# Power_DCDC.net
KiCad netlist of a schematic drawn in Altium Designer
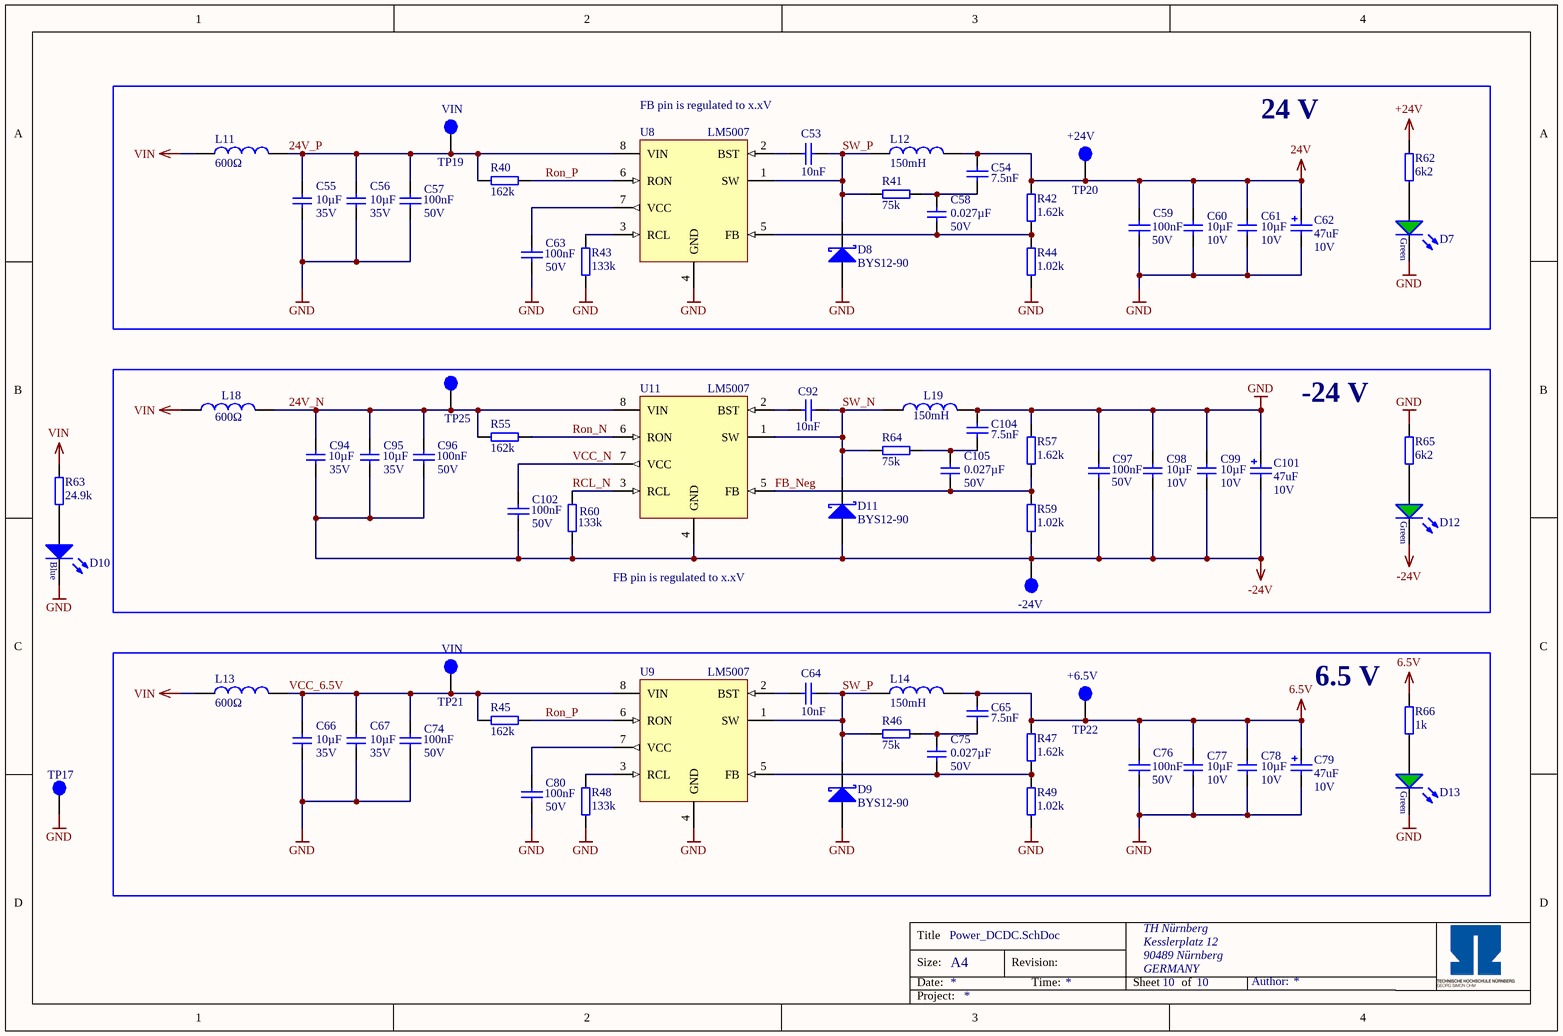
[diagram p0: Power_DCDC.SchDoc]

(export (version "E")
  (design (tool "Eeschema 10.0.6"))
  (components
    (comp (ref "-24V")
      (value "-6.5V")
      (footprint "TP_1mm")
      (description "Testpoint 1mm")
      (fields (field (name "CREATED") "2018_06_25_AGeiger"))
      (libsource (lib "UltraZohm_ADC") (part "TP_1mm"))
    )
    (comp (ref "C53")
      (value "10nF")
      (footprint "CAPC1608X07N")
      (fields (field (name "MF") "Würth") (field (name "MPN") "885012206065") (field (name "VOLTAGE") "25V"))
      (libsource (lib "UltraZohm_ADC") (part "Cap_0603"))
    )
    (comp (ref "C54")
      (value "7.5nF")
      (footprint "CAPC1608X07N")
      (fields
        (field (name "MF") "KEMET")
        (field (name "MPN") "C0603C752J3GACTU")
        (field (name "VOLTAGE") "25V")
      )
      (libsource (lib "UltraZohm_ADC") (part "Cap_0603"))
    )
    (comp (ref "C55")
      (value "10µF")
      (footprint "C_1206")
      (description "Capacitor 1206")
      (fields (field (name "TOLERANCE") "20%") (field (name "MF") "AVX") (field (name "VOLTAGE") "35V"))
      (libsource (lib "UltraZohm_ADC") (part "C_1206"))
    )
    (comp (ref "C56")
      (value "10µF")
      (footprint "C_1206")
      (description "Capacitor 1206")
      (fields (field (name "TOLERANCE") "20%") (field (name "MF") "AVX") (field (name "VOLTAGE") "35V"))
      (libsource (lib "UltraZohm_ADC") (part "C_1206"))
    )
    (comp (ref "C57")
      (value "100nF")
      (footprint "CAPC1608X07N")
      (fields
        (field (name "MF") "Yageo")
        (field (name "MPN") "CC0603KRX7R9BB104")
        (field (name "VOLTAGE") "50V")
        (field (name "TOLERANCE") "10%")
      )
      (libsource (lib "UltraZohm_ADC") (part "Cap_0603"))
    )
    (comp (ref "C58")
      (value "0.027µF")
      (footprint "C_1206")
      (description "Capacitor 1206")
      (fields
        (field (name "TOLERANCE") "5%")
        (field (name "MF") "Murata")
        (field (name "VOLTAGE") "50V")
        (field (name "CREATED") "2018_06_25_AGeiger")
      )
      (libsource (lib "UltraZohm_ADC") (part "C_1206"))
    )
    (comp (ref "C59")
      (value "100nF")
      (footprint "CAPC1608X07N")
      (fields
        (field (name "MF") "Yageo")
        (field (name "MPN") "CC0603KRX7R9BB104")
        (field (name "VOLTAGE") "50V")
      )
      (libsource (lib "UltraZohm_ADC") (part "Cap_0603"))
    )
    (comp (ref "C60")
      (value "10µF")
      (footprint "C_1206")
      (description "Capacitor 1206")
      (fields
        (field (name "TOLERANCE") "10%")
        (field (name "MF") "Samsung Electro-Mechanics")
        (field (name "VOLTAGE") "10V")
        (field (name "CREATED") "2020_09_17_Liegmann")
      )
      (libsource (lib "UltraZohm_ADC") (part "C_1206"))
    )
    (comp (ref "C61")
      (value "10µF")
      (footprint "C_1206")
      (description "Capacitor 1206")
      (fields
        (field (name "TOLERANCE") "10%")
        (field (name "MF") "Samsung Electro-Mechanics")
        (field (name "VOLTAGE") "10V")
        (field (name "CREATED") "2020_09_17_Liegmann")
      )
      (libsource (lib "UltraZohm_ADC") (part "C_1206"))
    )
    (comp (ref "C62")
      (value "47uF")
      (footprint "WCAP-ASLI_5x5.5")
      (description "WCAP-ASLI Aluminum Electrolytic Capacitor, V-Chip, SMT, D5xH5.5mm, 47uF, 10V")
      (fields
        (field (name "MPN") "865080242004")
        (field (name "MF") "Wurth Elektronik")
        (field (name "VOLTAGE") "10V")
      )
      (libsource (lib "UltraZohm_ADC") (part "865080142007"))
    )
    (comp (ref "C63")
      (value "100nF")
      (footprint "CAPC1608X07N")
      (fields
        (field (name "MF") "Yageo")
        (field (name "MPN") "CC0603KRX7R9BB104")
        (field (name "VOLTAGE") "50V")
        (field (name "TOLERANCE") "10%")
      )
      (libsource (lib "UltraZohm_ADC") (part "Cap_0603"))
    )
    (comp (ref "C64")
      (value "10nF")
      (footprint "CAPC1608X07N")
      (fields (field (name "MF") "Würth") (field (name "MPN") "885012206065") (field (name "VOLTAGE") "25V"))
      (libsource (lib "UltraZohm_ADC") (part "Cap_0603"))
    )
    (comp (ref "C65")
      (value "7.5nF")
      (footprint "CAPC1608X07N")
      (fields
        (field (name "MF") "KEMET")
        (field (name "MPN") "C0603C752J3GACTU")
        (field (name "VOLTAGE") "25V")
      )
      (libsource (lib "UltraZohm_ADC") (part "Cap_0603"))
    )
    (comp (ref "C66")
      (value "10µF")
      (footprint "C_1206")
      (description "Capacitor 1206")
      (fields (field (name "TOLERANCE") "20%") (field (name "MF") "AVX") (field (name "VOLTAGE") "35V"))
      (libsource (lib "UltraZohm_ADC") (part "C_1206"))
    )
    (comp (ref "C67")
      (value "10µF")
      (footprint "C_1206")
      (description "Capacitor 1206")
      (fields (field (name "TOLERANCE") "20%") (field (name "MF") "AVX") (field (name "VOLTAGE") "35V"))
      (libsource (lib "UltraZohm_ADC") (part "C_1206"))
    )
    (comp (ref "C74")
      (value "100nF")
      (footprint "CAPC1608X07N")
      (fields
        (field (name "MF") "Yageo")
        (field (name "MPN") "CC0603KRX7R9BB104")
        (field (name "VOLTAGE") "50V")
        (field (name "TOLERANCE") "10%")
      )
      (libsource (lib "UltraZohm_ADC") (part "Cap_0603"))
    )
    (comp (ref "C75")
      (value "0.027µF")
      (footprint "C_1206")
      (description "Capacitor 1206")
      (fields
        (field (name "TOLERANCE") "5%")
        (field (name "MF") "Murata")
        (field (name "VOLTAGE") "50V")
        (field (name "CREATED") "2018_06_25_AGeiger")
      )
      (libsource (lib "UltraZohm_ADC") (part "C_1206"))
    )
    (comp (ref "C76")
      (value "100nF")
      (footprint "CAPC1608X07N")
      (fields
        (field (name "MF") "Yageo")
        (field (name "MPN") "CC0603KRX7R9BB104")
        (field (name "VOLTAGE") "50V")
      )
      (libsource (lib "UltraZohm_ADC") (part "Cap_0603"))
    )
    (comp (ref "C77")
      (value "10µF")
      (footprint "C_1206")
      (description "Capacitor 1206")
      (fields
        (field (name "TOLERANCE") "10%")
        (field (name "MF") "Samsung Electro-Mechanics")
        (field (name "VOLTAGE") "10V")
        (field (name "CREATED") "2020_09_17_Liegmann")
      )
      (libsource (lib "UltraZohm_ADC") (part "C_1206"))
    )
    (comp (ref "C78")
      (value "10µF")
      (footprint "C_1206")
      (description "Capacitor 1206")
      (fields
        (field (name "TOLERANCE") "10%")
        (field (name "MF") "Samsung Electro-Mechanics")
        (field (name "VOLTAGE") "10V")
        (field (name "CREATED") "2020_09_17_Liegmann")
      )
      (libsource (lib "UltraZohm_ADC") (part "C_1206"))
    )
    (comp (ref "C79")
      (value "47uF")
      (footprint "WCAP-ASLI_5x5.5")
      (description "WCAP-ASLI Aluminum Electrolytic Capacitor, V-Chip, SMT, D5xH5.5mm, 47uF, 10V")
      (fields
        (field (name "MPN") "865080242004")
        (field (name "MF") "Wurth Elektronik")
        (field (name "VOLTAGE") "10V")
      )
      (libsource (lib "UltraZohm_ADC") (part "865080142007"))
    )
    (comp (ref "C80")
      (value "100nF")
      (footprint "CAPC1608X07N")
      (fields
        (field (name "MF") "Yageo")
        (field (name "MPN") "CC0603KRX7R9BB104")
        (field (name "VOLTAGE") "50V")
        (field (name "TOLERANCE") "10%")
      )
      (libsource (lib "UltraZohm_ADC") (part "Cap_0603"))
    )
    (comp (ref "C92")
      (value "10nF")
      (footprint "CAPC1608X07N")
      (fields
        (field (name "MF") "Würth Elektronik")
        (field (name "MPN") "885012206065")
        (field (name "VOLTAGE") "25V")
      )
      (libsource (lib "UltraZohm_ADC") (part "Cap_0603"))
    )
    (comp (ref "C94")
      (value "10µF")
      (footprint "C_1206")
      (description "Capacitor 1206")
      (fields (field (name "TOLERANCE") "20%") (field (name "MF") "AVX") (field (name "VOLTAGE") "35V"))
      (libsource (lib "UltraZohm_ADC") (part "C_1206"))
    )
    (comp (ref "C95")
      (value "10µF")
      (footprint "C_1206")
      (description "Capacitor 1206")
      (fields (field (name "TOLERANCE") "20%") (field (name "MF") "AVX") (field (name "VOLTAGE") "35V"))
      (libsource (lib "UltraZohm_ADC") (part "C_1206"))
    )
    (comp (ref "C96")
      (value "100nF")
      (footprint "CAPC1608X07N")
      (fields
        (field (name "MF") "Yageo")
        (field (name "MPN") "CC0603KRX7R9BB104")
        (field (name "VOLTAGE") "50V")
        (field (name "TOLERANCE") "10%")
      )
      (libsource (lib "UltraZohm_ADC") (part "Cap_0603"))
    )
    (comp (ref "C97")
      (value "100nF")
      (footprint "CAPC1608X07N")
      (fields
        (field (name "MF") "Yageo")
        (field (name "MPN") "CC0603KRX7R9BB104")
        (field (name "VOLTAGE") "50V")
        (field (name "TOLERANCE") "10%")
      )
      (libsource (lib "UltraZohm_ADC") (part "Cap_0603"))
    )
    (comp (ref "C98")
      (value "10µF")
      (footprint "C_1206")
      (description "Capacitor 1206")
      (fields
        (field (name "TOLERANCE") "10%")
        (field (name "MF") "Samsung Electro-Mechanics")
        (field (name "VOLTAGE") "10V")
        (field (name "CREATED") "2020_09_17_Liegmann")
      )
      (libsource (lib "UltraZohm_ADC") (part "C_1206"))
    )
    (comp (ref "C99")
      (value "10µF")
      (footprint "C_1206")
      (description "Capacitor 1206")
      (fields
        (field (name "TOLERANCE") "10%")
        (field (name "MF") "Samsung Electro-Mechanics")
        (field (name "VOLTAGE") "10V")
        (field (name "CREATED") "2020_09_17_Liegmann")
      )
      (libsource (lib "UltraZohm_ADC") (part "C_1206"))
    )
    (comp (ref "C101")
      (value "47uF")
      (footprint "WCAP-ASLI_5x5.5")
      (description "WCAP-ASLI Aluminum Electrolytic Capacitor, V-Chip, SMT, D5xH5.5mm, 47uF, 10V")
      (fields
        (field (name "MPN") "865080242004")
        (field (name "MF") "Wurth Elektronik")
        (field (name "VOLTAGE") "10V")
      )
      (libsource (lib "UltraZohm_ADC") (part "865080142007"))
    )
    (comp (ref "C102")
      (value "100nF")
      (footprint "CAPC1608X07N")
      (fields
        (field (name "MF") "Yageo")
        (field (name "MPN") "CC0603KRX7R9BB104")
        (field (name "VOLTAGE") "50V")
        (field (name "TOLERANCE") "10%")
      )
      (libsource (lib "UltraZohm_ADC") (part "Cap_0603"))
    )
    (comp (ref "C104")
      (value "7.5nF")
      (footprint "CAPC1608X07N")
      (fields
        (field (name "MF") "KEMET")
        (field (name "MPN") "C0603C752J3GACTU")
        (field (name "VOLTAGE") "25V")
      )
      (libsource (lib "UltraZohm_ADC") (part "Cap_0603"))
    )
    (comp (ref "C105")
      (value "0.027µF")
      (footprint "C_1206")
      (description "Capacitor 1206")
      (fields
        (field (name "TOLERANCE") "5%")
        (field (name "MF") "Murata")
        (field (name "VOLTAGE") "50V")
        (field (name "CREATED") "2018_06_25_AGeiger")
      )
      (libsource (lib "UltraZohm_ADC") (part "C_1206"))
    )
    (comp (ref "D7")
      (value "150060GS75000")
      (footprint "WL-SMCW_0603")
      (description "WL-SMCW SMD Mono-color Chip LED Waterclear, size 0603, Green, 3.2 V, 140°")
      (fields (field (name "MF") "Wuerth Elektronik") (field (name "CREATED") "2018_09_06_AGeiger"))
      (libsource (lib "UltraZohm_ADC") (part "LED_Green_0603"))
    )
    (comp (ref "D8")
      (value "BYS12-90")
      (footprint "DIOM4227X23N")
      (description "Schottky Diode")
      (fields (field (name "MF") "Vishay") (field (name "MPN") "BYS12-90-E3/TR3"))
      (libsource (lib "UltraZohm_ADC") (part "BYS12-90"))
    )
    (comp (ref "D9")
      (value "BYS12-90")
      (footprint "DIOM4227X23N")
      (description "Schottky Diode")
      (fields (field (name "MF") "Vishay") (field (name "MPN") "BYS12-90-E3/TR3"))
      (libsource (lib "UltraZohm_ADC") (part "BYS12-90"))
    )
    (comp (ref "D10")
      (value "150060BS75000")
      (footprint "WL-SMCW_0603")
      (description "WL-SMCW SMD Mono-color Chip LED Waterclear, size 0603, Blue, 3.2 V, 140°")
      (fields (field (name "MF") "Wuerth Elektronik") (field (name "CREATED") "2018_09_06_AGeiger"))
      (libsource (lib "UltraZohm_ADC") (part "LED_Blue_0603"))
    )
    (comp (ref "D11")
      (value "BYS12-90")
      (footprint "DIOM4227X23N")
      (description "Schottky Diode")
      (fields (field (name "MF") "Vishay") (field (name "MPN") "BYS12-90-E3/TR3"))
      (libsource (lib "UltraZohm_ADC") (part "BYS12-90"))
    )
    (comp (ref "D12")
      (value "150060GS75000")
      (footprint "WL-SMCW_0603")
      (description "WL-SMCW SMD Mono-color Chip LED Waterclear, size 0603, Green, 3.2 V, 140°")
      (fields (field (name "MF") "Wuerth Elektronik") (field (name "CREATED") "2018_09_06_AGeiger"))
      (libsource (lib "UltraZohm_ADC") (part "LED_Green_0603"))
    )
    (comp (ref "D13")
      (value "150060GS75000")
      (footprint "WL-SMCW_0603")
      (description "WL-SMCW SMD Mono-color Chip LED Waterclear, size 0603, Green, 3.2 V, 140°")
      (fields (field (name "MF") "Wuerth Elektronik") (field (name "CREATED") "2018_09_06_AGeiger"))
      (libsource (lib "UltraZohm_ADC") (part "LED_Green_0603"))
    )
    (comp (ref "L11")
      (value "600Ω")
      (footprint "WE-CBF_0805_High Current")
      (description "WE-CBF SMD EMI Suppression Ferrite Bead, 0805, 600Ω")
      (fields (field (name "MF") "Wurth Elektronik") (field (name "MPN") "742792040"))
      (libsource (lib "UltraZohm_ADC") (part "WE-CBF, 742792040"))
    )
    (comp (ref "L12")
      (value "150mH")
      (footprint "SMT_inductor_1050_Performance")
      (description "SMT power Inductor, 150uH, 320m DRC")
      (fields (field (name "MF") "EPCOS / TDK") (field (name "MPN") "B82464G4154M"))
      (libsource (lib "UltraZohm_ADC") (part "B82464G4154M"))
    )
    (comp (ref "L13")
      (value "600Ω")
      (footprint "WE-CBF_0805_High Current")
      (description "WE-CBF SMD EMI Suppression Ferrite Bead, 0805, 600Ω")
      (fields (field (name "MF") "Wurth Elektronik") (field (name "MPN") "742792040"))
      (libsource (lib "UltraZohm_ADC") (part "WE-CBF, 742792040"))
    )
    (comp (ref "L14")
      (value "150mH")
      (footprint "SMT_inductor_1050_Performance")
      (description "SMT power Inductor, 150uH, 320m DRC")
      (fields (field (name "MF") "EPCOS / TDK") (field (name "MPN") "B82464G4154M"))
      (libsource (lib "UltraZohm_ADC") (part "B82464G4154M"))
    )
    (comp (ref "L18")
      (value "600Ω")
      (footprint "WE-CBF_0805_High Current")
      (description "WE-CBF SMD EMI Suppression Ferrite Bead, 0805, 600Ω")
      (fields (field (name "MF") "Würth Elektronik") (field (name "MPN") "742792040"))
      (libsource (lib "UltraZohm_ADC") (part "WE-CBF, 742792040"))
    )
    (comp (ref "L19")
      (value "150mH")
      (footprint "SMT_inductor_1050_Performance")
      (description "SMT power Inductor, 150uH, 320m DRC")
      (fields (field (name "MF") "EPCOS / TDK") (field (name "MPN") "B82464G4154M"))
      (libsource (lib "UltraZohm_ADC") (part "B82464G4154M"))
    )
    (comp (ref "R40")
      (value "162k")
      (footprint "RESC1608X06N")
      (fields (field (name "MF") "Bourns") (field (name "MPN") "CR0603-FX-1623ELF"))
      (libsource (lib "UltraZohm_ADC") (part "R_0603"))
    )
    (comp (ref "R41")
      (value "75k")
      (footprint "RESC1608X06N")
      (fields (field (name "MF") "Yageo") (field (name "MPN") "AC0603FR-1375KL"))
      (libsource (lib "UltraZohm_ADC") (part "R_0603"))
    )
    (comp (ref "R42")
      (value "1.62k")
      (footprint "RESC1608X06N")
      (fields
        (field (name "MF") "Bourns")
        (field (name "MPN") "CR0603-FX-1621ELF")
        (field (name "TOLERANCE") "1%")
      )
      (libsource (lib "UltraZohm_ADC") (part "R_0603"))
    )
    (comp (ref "R43")
      (value "133k")
      (footprint "RESC1608X06N")
      (fields (field (name "MF") "Bourns") (field (name "MPN") "CR0603-FX-1333ELF"))
      (libsource (lib "UltraZohm_ADC") (part "R_0603"))
    )
    (comp (ref "R44")
      (value "1.02k")
      (footprint "RESC1608X06N")
      (fields
        (field (name "MF") "Bourns")
        (field (name "MPN") "CR0603-FX-1021ELF")
        (field (name "TOLERANCE") "1%")
      )
      (libsource (lib "UltraZohm_ADC") (part "R_0603"))
    )
    (comp (ref "R45")
      (value "162k")
      (footprint "RESC1608X06N")
      (fields (field (name "MF") "Bourns") (field (name "MPN") "CR0603-FX-1623ELF"))
      (libsource (lib "UltraZohm_ADC") (part "R_0603"))
    )
    (comp (ref "R46")
      (value "75k")
      (footprint "RESC1608X06N")
      (fields (field (name "MF") "Yageo") (field (name "MPN") "AC0603FR-1375KL"))
      (libsource (lib "UltraZohm_ADC") (part "R_0603"))
    )
    (comp (ref "R47")
      (value "1.62k")
      (footprint "RESC1608X06N")
      (fields
        (field (name "MF") "Bourns")
        (field (name "MPN") "CR0603-FX-1621ELF")
        (field (name "TOLERANCE") "1%")
      )
      (libsource (lib "UltraZohm_ADC") (part "R_0603"))
    )
    (comp (ref "R48")
      (value "133k")
      (footprint "RESC1608X06N")
      (fields (field (name "MF") "Bourns") (field (name "MPN") "CR0603-FX-1333ELF"))
      (libsource (lib "UltraZohm_ADC") (part "R_0603"))
    )
    (comp (ref "R49")
      (value "1.02k")
      (footprint "RESC1608X06N")
      (fields
        (field (name "MF") "Bourns")
        (field (name "MPN") "CR0603-FX-1021ELF")
        (field (name "TOLERANCE") "1%")
      )
      (libsource (lib "UltraZohm_ADC") (part "R_0603"))
    )
    (comp (ref "R55")
      (value "162k")
      (footprint "RESC1608X06N")
      (fields (field (name "MF") "Bourns") (field (name "MPN") "CR0603-FX-1623ELF"))
      (libsource (lib "UltraZohm_ADC") (part "R_0603"))
    )
    (comp (ref "R57")
      (value "1.62k")
      (footprint "RESC1608X06N")
      (fields
        (field (name "MF") "Bourns")
        (field (name "MPN") "CR0603-FX-1621ELF")
        (field (name "TOLERANCE") "1%")
      )
      (libsource (lib "UltraZohm_ADC") (part "R_0603"))
    )
    (comp (ref "R59")
      (value "1.02k")
      (footprint "RESC1608X06N")
      (fields
        (field (name "MF") "Bourns")
        (field (name "MPN") "CR0603-FX-1021ELF")
        (field (name "TOLERANCE") "1%")
      )
      (libsource (lib "UltraZohm_ADC") (part "R_0603"))
    )
    (comp (ref "R60")
      (value "133k")
      (footprint "RESC1608X06N")
      (fields (field (name "MF") "Bourns") (field (name "MPN") "CR0603-FX-1333ELF"))
      (libsource (lib "UltraZohm_ADC") (part "R_0603"))
    )
    (comp (ref "R62")
      (value "6k2")
      (footprint "RES 0603_1608")
      (description "SMD resistor E24 series")
      (fields
        (field (name "MANUFACTURER PART NUMBER") "RK73B1JTTD622J")
        (field (name "MANUFACTURER") "KOA Speer")
        (field (name "CREATED FROM") "MGremer")
      )
      (libsource (lib "user") (part "Resistor"))
    )
    (comp (ref "R63")
      (value "24.9k")
      (footprint "RESC1608X06N")
      (fields (field (name "MF") "Vishay / Dale") (field (name "MPN") "CRCW060324K9FKEAC"))
      (libsource (lib "UltraZohm_ADC") (part "R_0603"))
    )
    (comp (ref "R64")
      (value "75k")
      (footprint "RESC1608X06N")
      (fields (field (name "MF") "Yageo") (field (name "MPN") "AC0603FR-1375KL"))
      (libsource (lib "UltraZohm_ADC") (part "R_0603"))
    )
    (comp (ref "R65")
      (value "6k2")
      (footprint "RES 0603_1608")
      (description "SMD resistor E24 series")
      (fields
        (field (name "MANUFACTURER PART NUMBER") "RK73B1JTTD622J")
        (field (name "MANUFACTURER") "KOA Speer")
        (field (name "CREATED FROM") "MGremer")
      )
      (libsource (lib "user") (part "Resistor"))
    )
    (comp (ref "R66")
      (value "1k")
      (footprint "RES 0603_1608")
      (description "SMD resistor E24 series")
      (fields
        (field (name "MANUFACTURER PART NUMBER") "RK73B1JTTDD102J")
        (field (name "MANUFACTURER") "KOA Speer")
        (field (name "CREATED FROM") "MGremer")
      )
      (libsource (lib "user") (part "Resistor"))
    )
    (comp (ref "TP17")
      (value "GND")
      (footprint "TP_1mm")
      (description "Testpoint 1mm")
      (fields (field (name "CREATED") "2018_06_25_AGeiger"))
      (libsource (lib "UltraZOhm_CarrierBoard") (part "TP_1mm"))
    )
    (comp (ref "TP19")
      (value "VIN")
      (footprint "TP_1mm")
      (description "Testpoint 1mm")
      (fields (field (name "CREATED") "2018_06_25_AGeiger"))
      (libsource (lib "UltraZOhm_CarrierBoard") (part "TP_1mm"))
    )
    (comp (ref "TP20")
      (value "+24V")
      (footprint "TP_1mm")
      (description "Testpoint 1mm")
      (fields (field (name "CREATED") "2018_06_25_AGeiger"))
      (libsource (lib "UltraZOhm_CarrierBoard") (part "TP_1mm"))
    )
    (comp (ref "TP21")
      (value "VIN")
      (footprint "TP_1mm")
      (description "Testpoint 1mm")
      (fields (field (name "CREATED") "2018_06_25_AGeiger"))
      (libsource (lib "UltraZOhm_CarrierBoard") (part "TP_1mm"))
    )
    (comp (ref "TP22")
      (value "+6.5V")
      (footprint "TP_1mm")
      (description "Testpoint 1mm")
      (fields (field (name "CREATED") "2018_06_25_AGeiger"))
      (libsource (lib "UltraZOhm_CarrierBoard") (part "TP_1mm"))
    )
    (comp (ref "TP25")
      (value "VIN")
      (footprint "TP_1mm")
      (description "Testpoint 1mm")
      (fields (field (name "CREATED") "2018_06_25_AGeiger"))
      (libsource (lib "UltraZohm_ADC") (part "TP_1mm"))
    )
    (comp (ref "U8")
      (value "LM5007")
      (footprint "TSOP65P490X110-8N")
      (description "Buck Converter, 9-75Vin, 2.5-73Vout")
      (fields (field (name "MF") "Texas Instruments") (field (name "MPN") "LM5007MM/NOPB"))
      (libsource (lib "UltraZohm_ADC") (part "LM5007"))
    )
    (comp (ref "U9")
      (value "LM5007")
      (footprint "TSOP65P490X110-8N")
      (description "Buck Converter, 9-75Vin, 2.5-73Vout")
      (fields (field (name "MF") "Texas Instruments") (field (name "MPN") "LM5007MM/NOPB"))
      (libsource (lib "UltraZohm_ADC") (part "LM5007"))
    )
    (comp (ref "U11")
      (value "LM5007")
      (footprint "TSOP65P490X110-8N")
      (description "Buck Converter, 9-75Vin, 2.5-73Vout")
      (fields (field (name "MF") "Texas Instruments") (field (name "MPN") "LM5007MM/NOPB"))
      (libsource (lib "UltraZohm_ADC") (part "LM5007"))
    )
  )
  (nets
    (net (code "1") (name "+24V") (class "Default")
      (node (ref "R62") (pin "2") (pinfunction "2_2") (pintype "passive"))
    )
    (net (code "2") (name "-24V") (class "Default")
      (node (ref "-24V") (pin "1") (pintype "passive"))
      (node (ref "C101") (pin "1") (pinfunction "N_1") (pintype "passive"))
      (node (ref "C102") (pin "2") (pinfunction "2_2") (pintype "passive"))
      (node (ref "C94") (pin "1") (pinfunction "1_1") (pintype "passive"))
      (node (ref "C95") (pin "1") (pinfunction "1_1") (pintype "passive"))
      (node (ref "C96") (pin "2") (pinfunction "2_2") (pintype "passive"))
      (node (ref "C97") (pin "1") (pinfunction "1_1") (pintype "passive"))
      (node (ref "C98") (pin "1") (pinfunction "1_1") (pintype "passive"))
      (node (ref "C99") (pin "1") (pinfunction "1_1") (pintype "passive"))
      (node (ref "D11") (pin "2") (pinfunction "A_2") (pintype "passive"))
      (node (ref "D12") (pin "1") (pinfunction "K_1") (pintype "passive"))
      (node (ref "R59") (pin "2") (pintype "passive"))
      (node (ref "R60") (pin "1") (pintype "passive"))
      (node (ref "U11") (pin "4") (pinfunction "GND_4") (pintype "power_in"))
    )
    (net (code "3") (name "/24V_N") (class "Default")
      (node (ref "C94") (pin "2") (pinfunction "2_2") (pintype "passive"))
      (node (ref "C95") (pin "2") (pinfunction "2_2") (pintype "passive"))
      (node (ref "C96") (pin "1") (pinfunction "1_1") (pintype "passive"))
      (node (ref "L18") (pin "2") (pinfunction "2_2") (pintype "passive"))
      (node (ref "R55") (pin "2") (pintype "passive"))
      (node (ref "TP25") (pin "1") (pintype "passive"))
      (node (ref "U11") (pin "8") (pinfunction "VIN_8") (pintype "power_in"))
    )
    (net (code "4") (name "/24V_P") (class "Default")
      (node (ref "C55") (pin "2") (pinfunction "2_2") (pintype "passive"))
      (node (ref "C56") (pin "2") (pinfunction "2_2") (pintype "passive"))
      (node (ref "C57") (pin "1") (pinfunction "1_1") (pintype "passive"))
      (node (ref "L11") (pin "2") (pinfunction "2_2") (pintype "passive"))
      (node (ref "R40") (pin "1") (pintype "passive"))
      (node (ref "TP19") (pin "1") (pintype "passive"))
      (node (ref "U8") (pin "8") (pinfunction "VIN_8") (pintype "power_in"))
    )
    (net (code "5") (name "/FB_Neg") (class "Default")
      (node (ref "C105") (pin "1") (pinfunction "1_1") (pintype "passive"))
      (node (ref "R57") (pin "2") (pintype "passive"))
      (node (ref "R59") (pin "1") (pintype "passive"))
      (node (ref "U11") (pin "5") (pinfunction "FB_5") (pintype "input"))
    )
    (net (code "6") (name "/RCL_N") (class "Default")
      (node (ref "R60") (pin "2") (pintype "passive"))
      (node (ref "U11") (pin "3") (pinfunction "RCL_3") (pintype "input"))
    )
    (net (code "7") (name "/Ron_N") (class "Default")
      (node (ref "R55") (pin "1") (pintype "passive"))
      (node (ref "U11") (pin "6") (pinfunction "RON_6") (pintype "input"))
    )
    (net (code "8") (name "/Ron_P") (class "Default")
      (node (ref "R40") (pin "2") (pintype "passive"))
      (node (ref "R45") (pin "2") (pintype "passive"))
      (node (ref "U8") (pin "6") (pinfunction "RON_6") (pintype "input"))
      (node (ref "U9") (pin "6") (pinfunction "RON_6") (pintype "input"))
    )
    (net (code "9") (name "/SW_N") (class "Default")
      (node (ref "C92") (pin "1") (pinfunction "1_1") (pintype "passive"))
      (node (ref "D11") (pin "1") (pinfunction "K_1") (pintype "passive"))
      (node (ref "L19") (pin "1") (pinfunction "1_1") (pintype "passive"))
      (node (ref "R64") (pin "1") (pintype "passive"))
      (node (ref "U11") (pin "1") (pinfunction "SW_1") (pintype "power_in"))
    )
    (net (code "10") (name "/SW_P") (class "Default")
      (node (ref "C53") (pin "2") (pinfunction "2_2") (pintype "passive"))
      (node (ref "C64") (pin "2") (pinfunction "2_2") (pintype "passive"))
      (node (ref "D8") (pin "1") (pinfunction "K_1") (pintype "passive"))
      (node (ref "D9") (pin "1") (pinfunction "K_1") (pintype "passive"))
      (node (ref "L12") (pin "1") (pinfunction "1_1") (pintype "passive"))
      (node (ref "L14") (pin "1") (pinfunction "1_1") (pintype "passive"))
      (node (ref "R41") (pin "1") (pintype "passive"))
      (node (ref "R46") (pin "1") (pintype "passive"))
      (node (ref "U8") (pin "1") (pinfunction "SW_1") (pintype "power_in"))
      (node (ref "U9") (pin "1") (pinfunction "SW_1") (pintype "power_in"))
    )
    (net (code "11") (name "/VCC_6.5V") (class "Default")
      (node (ref "C66") (pin "2") (pinfunction "2_2") (pintype "passive"))
      (node (ref "C67") (pin "2") (pinfunction "2_2") (pintype "passive"))
      (node (ref "C74") (pin "1") (pinfunction "1_1") (pintype "passive"))
      (node (ref "L13") (pin "2") (pinfunction "2_2") (pintype "passive"))
      (node (ref "R45") (pin "1") (pintype "passive"))
      (node (ref "TP21") (pin "1") (pintype "passive"))
      (node (ref "U9") (pin "8") (pinfunction "VIN_8") (pintype "power_in"))
    )
    (net (code "12") (name "/VCC_N") (class "Default")
      (node (ref "C102") (pin "1") (pinfunction "1_1") (pintype "passive"))
      (node (ref "U11") (pin "7") (pinfunction "VCC_7") (pintype "output"))
    )
    (net (code "13") (name "6.5V") (class "Default")
      (node (ref "C65") (pin "1") (pinfunction "1_1") (pintype "passive"))
      (node (ref "C76") (pin "2") (pinfunction "2_2") (pintype "passive"))
      (node (ref "C77") (pin "2") (pinfunction "2_2") (pintype "passive"))
      (node (ref "C78") (pin "2") (pinfunction "2_2") (pintype "passive"))
      (node (ref "C79") (pin "2") (pinfunction "P_2") (pintype "passive"))
      (node (ref "L14") (pin "2") (pinfunction "2_2") (pintype "passive"))
      (node (ref "R47") (pin "2") (pintype "passive"))
      (node (ref "R66") (pin "2") (pinfunction "2_2") (pintype "passive"))
      (node (ref "TP22") (pin "1") (pintype "passive"))
    )
    (net (code "14") (name "24V") (class "Default")
      (node (ref "C54") (pin "1") (pinfunction "1_1") (pintype "passive"))
      (node (ref "C59") (pin "2") (pinfunction "2_2") (pintype "passive"))
      (node (ref "C60") (pin "2") (pinfunction "2_2") (pintype "passive"))
      (node (ref "C61") (pin "2") (pinfunction "2_2") (pintype "passive"))
      (node (ref "C62") (pin "2") (pinfunction "P_2") (pintype "passive"))
      (node (ref "L12") (pin "2") (pinfunction "2_2") (pintype "passive"))
      (node (ref "R42") (pin "2") (pintype "passive"))
      (node (ref "TP20") (pin "1") (pintype "passive"))
    )
    (net (code "15") (name "GND") (class "Default")
      (node (ref "C101") (pin "2") (pinfunction "P_2") (pintype "passive"))
      (node (ref "C104") (pin "1") (pinfunction "1_1") (pintype "passive"))
      (node (ref "C55") (pin "1") (pinfunction "1_1") (pintype "passive"))
      (node (ref "C56") (pin "1") (pinfunction "1_1") (pintype "passive"))
      (node (ref "C57") (pin "2") (pinfunction "2_2") (pintype "passive"))
      (node (ref "C59") (pin "1") (pinfunction "1_1") (pintype "passive"))
      (node (ref "C60") (pin "1") (pinfunction "1_1") (pintype "passive"))
      (node (ref "C61") (pin "1") (pinfunction "1_1") (pintype "passive"))
      (node (ref "C62") (pin "1") (pinfunction "N_1") (pintype "passive"))
      (node (ref "C63") (pin "2") (pinfunction "2_2") (pintype "passive"))
      (node (ref "C66") (pin "1") (pinfunction "1_1") (pintype "passive"))
      (node (ref "C67") (pin "1") (pinfunction "1_1") (pintype "passive"))
      (node (ref "C74") (pin "2") (pinfunction "2_2") (pintype "passive"))
      (node (ref "C76") (pin "1") (pinfunction "1_1") (pintype "passive"))
      (node (ref "C77") (pin "1") (pinfunction "1_1") (pintype "passive"))
      (node (ref "C78") (pin "1") (pinfunction "1_1") (pintype "passive"))
      (node (ref "C79") (pin "1") (pinfunction "N_1") (pintype "passive"))
      (node (ref "C80") (pin "2") (pinfunction "2_2") (pintype "passive"))
      (node (ref "C97") (pin "2") (pinfunction "2_2") (pintype "passive"))
      (node (ref "C98") (pin "2") (pinfunction "2_2") (pintype "passive"))
      (node (ref "C99") (pin "2") (pinfunction "2_2") (pintype "passive"))
      (node (ref "D10") (pin "1") (pinfunction "K_1") (pintype "passive"))
      (node (ref "D13") (pin "1") (pinfunction "K_1") (pintype "passive"))
      (node (ref "D7") (pin "1") (pinfunction "K_1") (pintype "passive"))
      (node (ref "D8") (pin "2") (pinfunction "A_2") (pintype "passive"))
      (node (ref "D9") (pin "2") (pinfunction "A_2") (pintype "passive"))
      (node (ref "L19") (pin "2") (pinfunction "2_2") (pintype "passive"))
      (node (ref "R43") (pin "1") (pintype "passive"))
      (node (ref "R44") (pin "1") (pintype "passive"))
      (node (ref "R48") (pin "1") (pintype "passive"))
      (node (ref "R49") (pin "1") (pintype "passive"))
      (node (ref "R57") (pin "1") (pintype "passive"))
      (node (ref "R65") (pin "2") (pinfunction "2_2") (pintype "passive"))
      (node (ref "TP17") (pin "1") (pintype "passive"))
      (node (ref "U8") (pin "4") (pinfunction "GND_4") (pintype "power_in"))
      (node (ref "U9") (pin "4") (pinfunction "GND_4") (pintype "power_in"))
    )
    (net (code "16") (name "Net-(C54-Pad2)") (class "Default")
      (node (ref "C54") (pin "2") (pinfunction "2_2") (pintype "passive"))
      (node (ref "C58") (pin "2") (pinfunction "2_2") (pintype "passive"))
      (node (ref "R41") (pin "2") (pintype "passive"))
    )
    (net (code "17") (name "Net-(C65-Pad2)") (class "Default")
      (node (ref "C65") (pin "2") (pinfunction "2_2") (pintype "passive"))
      (node (ref "C75") (pin "2") (pinfunction "2_2") (pintype "passive"))
      (node (ref "R46") (pin "2") (pintype "passive"))
    )
    (net (code "18") (name "Net-(C104-Pad2)") (class "Default")
      (node (ref "C104") (pin "2") (pinfunction "2_2") (pintype "passive"))
      (node (ref "C105") (pin "2") (pinfunction "2_2") (pintype "passive"))
      (node (ref "R64") (pin "2") (pintype "passive"))
    )
    (net (code "19") (name "Net-(D7-A)") (class "Default")
      (node (ref "D7") (pin "2") (pinfunction "A_2") (pintype "passive"))
      (node (ref "R62") (pin "1") (pinfunction "1_1") (pintype "passive"))
    )
    (net (code "20") (name "Net-(D10-A)") (class "Default")
      (node (ref "D10") (pin "2") (pinfunction "A_2") (pintype "passive"))
      (node (ref "R63") (pin "1") (pintype "passive"))
    )
    (net (code "21") (name "Net-(D12-A)") (class "Default")
      (node (ref "D12") (pin "2") (pinfunction "A_2") (pintype "passive"))
      (node (ref "R65") (pin "1") (pinfunction "1_1") (pintype "passive"))
    )
    (net (code "22") (name "Net-(D13-A)") (class "Default")
      (node (ref "D13") (pin "2") (pinfunction "A_2") (pintype "passive"))
      (node (ref "R66") (pin "1") (pinfunction "1_1") (pintype "passive"))
    )
    (net (code "23") (name "Net-(U8-BST)") (class "Default")
      (node (ref "C53") (pin "1") (pinfunction "1_1") (pintype "passive"))
      (node (ref "U8") (pin "2") (pinfunction "BST_2") (pintype "input"))
    )
    (net (code "24") (name "Net-(U8-FB)") (class "Default")
      (node (ref "C58") (pin "1") (pinfunction "1_1") (pintype "passive"))
      (node (ref "R42") (pin "1") (pintype "passive"))
      (node (ref "R44") (pin "2") (pintype "passive"))
      (node (ref "U8") (pin "5") (pinfunction "FB_5") (pintype "input"))
    )
    (net (code "25") (name "Net-(U8-RCL)") (class "Default")
      (node (ref "R43") (pin "2") (pintype "passive"))
      (node (ref "U8") (pin "3") (pinfunction "RCL_3") (pintype "input"))
    )
    (net (code "26") (name "Net-(U8-VCC)") (class "Default")
      (node (ref "C63") (pin "1") (pinfunction "1_1") (pintype "passive"))
      (node (ref "U8") (pin "7") (pinfunction "VCC_7") (pintype "output"))
    )
    (net (code "27") (name "Net-(U9-BST)") (class "Default")
      (node (ref "C64") (pin "1") (pinfunction "1_1") (pintype "passive"))
      (node (ref "U9") (pin "2") (pinfunction "BST_2") (pintype "input"))
    )
    (net (code "28") (name "Net-(U9-FB)") (class "Default")
      (node (ref "C75") (pin "1") (pinfunction "1_1") (pintype "passive"))
      (node (ref "R47") (pin "1") (pintype "passive"))
      (node (ref "R49") (pin "2") (pintype "passive"))
      (node (ref "U9") (pin "5") (pinfunction "FB_5") (pintype "input"))
    )
    (net (code "29") (name "Net-(U9-RCL)") (class "Default")
      (node (ref "R48") (pin "2") (pintype "passive"))
      (node (ref "U9") (pin "3") (pinfunction "RCL_3") (pintype "input"))
    )
    (net (code "30") (name "Net-(U9-VCC)") (class "Default")
      (node (ref "C80") (pin "1") (pinfunction "1_1") (pintype "passive"))
      (node (ref "U9") (pin "7") (pinfunction "VCC_7") (pintype "output"))
    )
    (net (code "31") (name "Net-(U11-BST)") (class "Default")
      (node (ref "C92") (pin "2") (pinfunction "2_2") (pintype "passive"))
      (node (ref "U11") (pin "2") (pinfunction "BST_2") (pintype "input"))
    )
    (net (code "32") (name "VIN") (class "Default")
      (node (ref "L11") (pin "1") (pinfunction "1_1") (pintype "passive"))
      (node (ref "L13") (pin "1") (pinfunction "1_1") (pintype "passive"))
      (node (ref "L18") (pin "1") (pinfunction "1_1") (pintype "passive"))
      (node (ref "R63") (pin "2") (pintype "passive"))
    )
  )
)
